# tarjeta.net
KiCad netlist of a schematic drawn in EAGLE
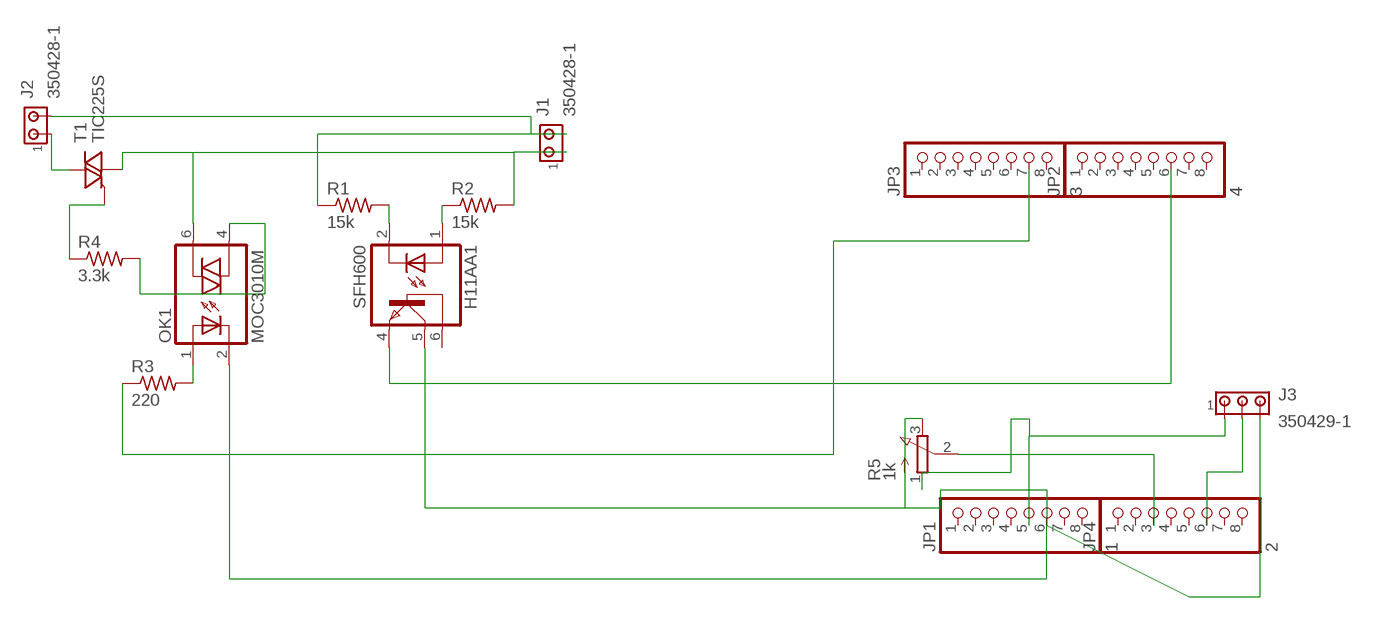
[diagram p0: schematic, sheet 1]

(export (version "E")
  (design (tool "Eeschema 10.0.6"))
  (components
    (comp (ref "H11AA1")
      (value "SFH600")
      (footprint "eagle-import:DIL06")
      (libsource (lib "eagle-import") (part "SFH600"))
    )
    (comp (ref "J1")
      (value "350428-1")
      (footprint "eagle-import:350428-1")
      (libsource (lib "eagle-import") (part "350428-1"))
    )
    (comp (ref "J2")
      (value "350428-1")
      (footprint "eagle-import:350428-1")
      (libsource (lib "eagle-import") (part "350428-1"))
    )
    (comp (ref "J3")
      (value "350429-1")
      (footprint "eagle-import:350429-1")
      (libsource (lib "eagle-import") (part "350429-1"))
    )
    (comp (ref "JP1")
      (value "1")
      (footprint "eagle-import:1X08_90")
      (libsource (lib "eagle-import") (part "PINHD-1X8/90"))
    )
    (comp (ref "JP2")
      (value "4")
      (footprint "eagle-import:1X08_90")
      (libsource (lib "eagle-import") (part "PINHD-1X8/90"))
    )
    (comp (ref "JP3")
      (value "3")
      (footprint "eagle-import:1X08_90")
      (libsource (lib "eagle-import") (part "PINHD-1X8/90"))
    )
    (comp (ref "JP4")
      (value "2")
      (footprint "eagle-import:1X08_90")
      (libsource (lib "eagle-import") (part "PINHD-1X8/90"))
    )
    (comp (ref "OK1")
      (value "MOC3010M")
      (footprint "eagle-import:DIL06")
      (libsource (lib "eagle-import") (part "MOC30M10"))
    )
    (comp (ref "R1")
      (value "15k")
      (footprint "eagle-import:0207_10")
      (libsource (lib "eagle-import") (part "R-US_0207/10"))
    )
    (comp (ref "R2")
      (value "15k")
      (footprint "eagle-import:0207_10")
      (libsource (lib "eagle-import") (part "R-US_0207/10"))
    )
    (comp (ref "R3")
      (value "220")
      (footprint "eagle-import:0207_10")
      (libsource (lib "eagle-import") (part "R-US_0207/10"))
    )
    (comp (ref "R4")
      (value "3.3k")
      (footprint "eagle-import:0207_10")
      (libsource (lib "eagle-import") (part "R-US_0207/10"))
    )
    (comp (ref "R5")
      (value "1k")
      (footprint "eagle-import:3RP_1610N")
      (libsource (lib "eagle-import") (part "3RP/1610N"))
    )
    (comp (ref "T1")
      (value "TIC225S")
      (footprint "eagle-import:TO220DS")
      (libsource (lib "eagle-import") (part "TIC225S"))
    )
  )
  (nets
    (net (code "1") (name "Net-(H11AA1-A)") (class "Default")
      (node (ref "H11AA1") (pin "1") (pinfunction "A_1") (pintype "passive"))
      (node (ref "R2") (pin "1") (pinfunction "1_1") (pintype "passive"))
    )
    (net (code "2") (name "Net-(H11AA1-C)") (class "Default")
      (node (ref "H11AA1") (pin "2") (pinfunction "C_2") (pintype "passive"))
      (node (ref "R1") (pin "2") (pinfunction "2_2") (pintype "passive"))
    )
    (net (code "3") (name "Net-(H11AA1-COL)") (class "Default")
      (node (ref "H11AA1") (pin "5") (pinfunction "COL_5") (pintype "passive"))
      (node (ref "J3") (pin "3") (pinfunction "3_3") (pintype "passive"))
      (node (ref "JP1") (pin "6") (pinfunction "6_6") (pintype "passive"))
      (node (ref "OK1") (pin "2") (pinfunction "C_2") (pintype "passive"))
      (node (ref "R5") (pin "3") (pinfunction "E_3") (pintype "passive"))
    )
    (net (code "4") (name "Net-(H11AA1-EMI)") (class "Default")
      (node (ref "H11AA1") (pin "4") (pinfunction "EMI_4") (pintype "passive"))
      (node (ref "JP2") (pin "6") (pinfunction "6_6") (pintype "passive"))
    )
    (net (code "5") (name "Net-(J1-Pad2)") (class "Default")
      (node (ref "J1") (pin "2") (pinfunction "2_2") (pintype "passive"))
      (node (ref "J2") (pin "2") (pinfunction "2_2") (pintype "passive"))
      (node (ref "R1") (pin "1") (pinfunction "1_1") (pintype "passive"))
    )
    (net (code "6") (name "Net-(J2-Pad1)") (class "Default")
      (node (ref "J2") (pin "1") (pinfunction "1_1") (pintype "passive"))
      (node (ref "T1") (pin "A2") (pinfunction "A2_A2") (pintype "passive"))
    )
    (net (code "7") (name "Net-(J3-Pad2)") (class "Default")
      (node (ref "J3") (pin "2") (pinfunction "2_2") (pintype "passive"))
      (node (ref "JP4") (pin "6") (pinfunction "6_6") (pintype "passive"))
    )
    (net (code "8") (name "Net-(JP3-Pad7)") (class "Default")
      (node (ref "JP3") (pin "7") (pinfunction "7_7") (pintype "passive"))
      (node (ref "R3") (pin "1") (pinfunction "1_1") (pintype "passive"))
    )
    (net (code "9") (name "Net-(OK1-A)") (class "Default")
      (node (ref "OK1") (pin "1") (pinfunction "A_1") (pintype "passive"))
      (node (ref "R3") (pin "2") (pinfunction "2_2") (pintype "passive"))
    )
    (net (code "10") (name "Net-(OK1-A1)") (class "Default")
      (node (ref "OK1") (pin "4") (pinfunction "A1_4") (pintype "passive"))
      (node (ref "R4") (pin "2") (pinfunction "2_2") (pintype "passive"))
    )
    (net (code "11") (name "Net-(OK1-A2)") (class "Default")
      (node (ref "J1") (pin "1") (pinfunction "1_1") (pintype "passive"))
      (node (ref "OK1") (pin "6") (pinfunction "A2_6") (pintype "passive"))
      (node (ref "R2") (pin "2") (pinfunction "2_2") (pintype "passive"))
      (node (ref "T1") (pin "A1") (pinfunction "A1_A1") (pintype "passive"))
    )
    (net (code "12") (name "Net-(R4-Pad1)") (class "Default")
      (node (ref "R4") (pin "1") (pinfunction "1_1") (pintype "passive"))
      (node (ref "T1") (pin "G") (pinfunction "G_G") (pintype "passive"))
    )
    (net (code "13") (name "Net-(R5-A)") (class "Default")
      (node (ref "J3") (pin "1") (pinfunction "1_1") (pintype "passive"))
      (node (ref "JP1") (pin "5") (pinfunction "5_5") (pintype "passive"))
      (node (ref "R5") (pin "1") (pinfunction "A_1") (pintype "passive"))
    )
    (net (code "14") (name "Net-(R5-S)") (class "Default")
      (node (ref "JP4") (pin "3") (pinfunction "3_3") (pintype "passive"))
      (node (ref "R5") (pin "2") (pinfunction "S_2") (pintype "passive"))
    )
    (net (code "15") (name "unconnected-(H11AA1-BAS-Pad6)") (class "Default")
      (node (ref "H11AA1") (pin "6") (pinfunction "BAS_6") (pintype "passive"))
    )
    (net (code "16") (name "unconnected-(JP1-Pad1)") (class "Default")
      (node (ref "JP1") (pin "1") (pinfunction "1_1") (pintype "passive"))
    )
    (net (code "17") (name "unconnected-(JP1-Pad2)") (class "Default")
      (node (ref "JP1") (pin "2") (pinfunction "2_2") (pintype "passive"))
    )
    (net (code "18") (name "unconnected-(JP1-Pad3)") (class "Default")
      (node (ref "JP1") (pin "3") (pinfunction "3_3") (pintype "passive"))
    )
    (net (code "19") (name "unconnected-(JP1-Pad4)") (class "Default")
      (node (ref "JP1") (pin "4") (pinfunction "4_4") (pintype "passive"))
    )
    (net (code "20") (name "unconnected-(JP1-Pad7)") (class "Default")
      (node (ref "JP1") (pin "7") (pinfunction "7_7") (pintype "passive"))
    )
    (net (code "21") (name "unconnected-(JP1-Pad8)") (class "Default")
      (node (ref "JP1") (pin "8") (pinfunction "8_8") (pintype "passive"))
    )
    (net (code "22") (name "unconnected-(JP2-Pad1)") (class "Default")
      (node (ref "JP2") (pin "1") (pinfunction "1_1") (pintype "passive"))
    )
    (net (code "23") (name "unconnected-(JP2-Pad2)") (class "Default")
      (node (ref "JP2") (pin "2") (pinfunction "2_2") (pintype "passive"))
    )
    (net (code "24") (name "unconnected-(JP2-Pad3)") (class "Default")
      (node (ref "JP2") (pin "3") (pinfunction "3_3") (pintype "passive"))
    )
    (net (code "25") (name "unconnected-(JP2-Pad4)") (class "Default")
      (node (ref "JP2") (pin "4") (pinfunction "4_4") (pintype "passive"))
    )
    (net (code "26") (name "unconnected-(JP2-Pad5)") (class "Default")
      (node (ref "JP2") (pin "5") (pinfunction "5_5") (pintype "passive"))
    )
    (net (code "27") (name "unconnected-(JP2-Pad7)") (class "Default")
      (node (ref "JP2") (pin "7") (pinfunction "7_7") (pintype "passive"))
    )
    (net (code "28") (name "unconnected-(JP2-Pad8)") (class "Default")
      (node (ref "JP2") (pin "8") (pinfunction "8_8") (pintype "passive"))
    )
    (net (code "29") (name "unconnected-(JP3-Pad1)") (class "Default")
      (node (ref "JP3") (pin "1") (pinfunction "1_1") (pintype "passive"))
    )
    (net (code "30") (name "unconnected-(JP3-Pad2)") (class "Default")
      (node (ref "JP3") (pin "2") (pinfunction "2_2") (pintype "passive"))
    )
    (net (code "31") (name "unconnected-(JP3-Pad3)") (class "Default")
      (node (ref "JP3") (pin "3") (pinfunction "3_3") (pintype "passive"))
    )
    (net (code "32") (name "unconnected-(JP3-Pad4)") (class "Default")
      (node (ref "JP3") (pin "4") (pinfunction "4_4") (pintype "passive"))
    )
    (net (code "33") (name "unconnected-(JP3-Pad5)") (class "Default")
      (node (ref "JP3") (pin "5") (pinfunction "5_5") (pintype "passive"))
    )
    (net (code "34") (name "unconnected-(JP3-Pad6)") (class "Default")
      (node (ref "JP3") (pin "6") (pinfunction "6_6") (pintype "passive"))
    )
    (net (code "35") (name "unconnected-(JP3-Pad8)") (class "Default")
      (node (ref "JP3") (pin "8") (pinfunction "8_8") (pintype "passive"))
    )
    (net (code "36") (name "unconnected-(JP4-Pad1)") (class "Default")
      (node (ref "JP4") (pin "1") (pinfunction "1_1") (pintype "passive"))
    )
    (net (code "37") (name "unconnected-(JP4-Pad2)") (class "Default")
      (node (ref "JP4") (pin "2") (pinfunction "2_2") (pintype "passive"))
    )
    (net (code "38") (name "unconnected-(JP4-Pad4)") (class "Default")
      (node (ref "JP4") (pin "4") (pinfunction "4_4") (pintype "passive"))
    )
    (net (code "39") (name "unconnected-(JP4-Pad5)") (class "Default")
      (node (ref "JP4") (pin "5") (pinfunction "5_5") (pintype "passive"))
    )
    (net (code "40") (name "unconnected-(JP4-Pad7)") (class "Default")
      (node (ref "JP4") (pin "7") (pinfunction "7_7") (pintype "passive"))
    )
    (net (code "41") (name "unconnected-(JP4-Pad8)") (class "Default")
      (node (ref "JP4") (pin "8") (pinfunction "8_8") (pintype "passive"))
    )
  )
)
